# schematic.net
KiCad netlist of a schematic drawn in EAGLE
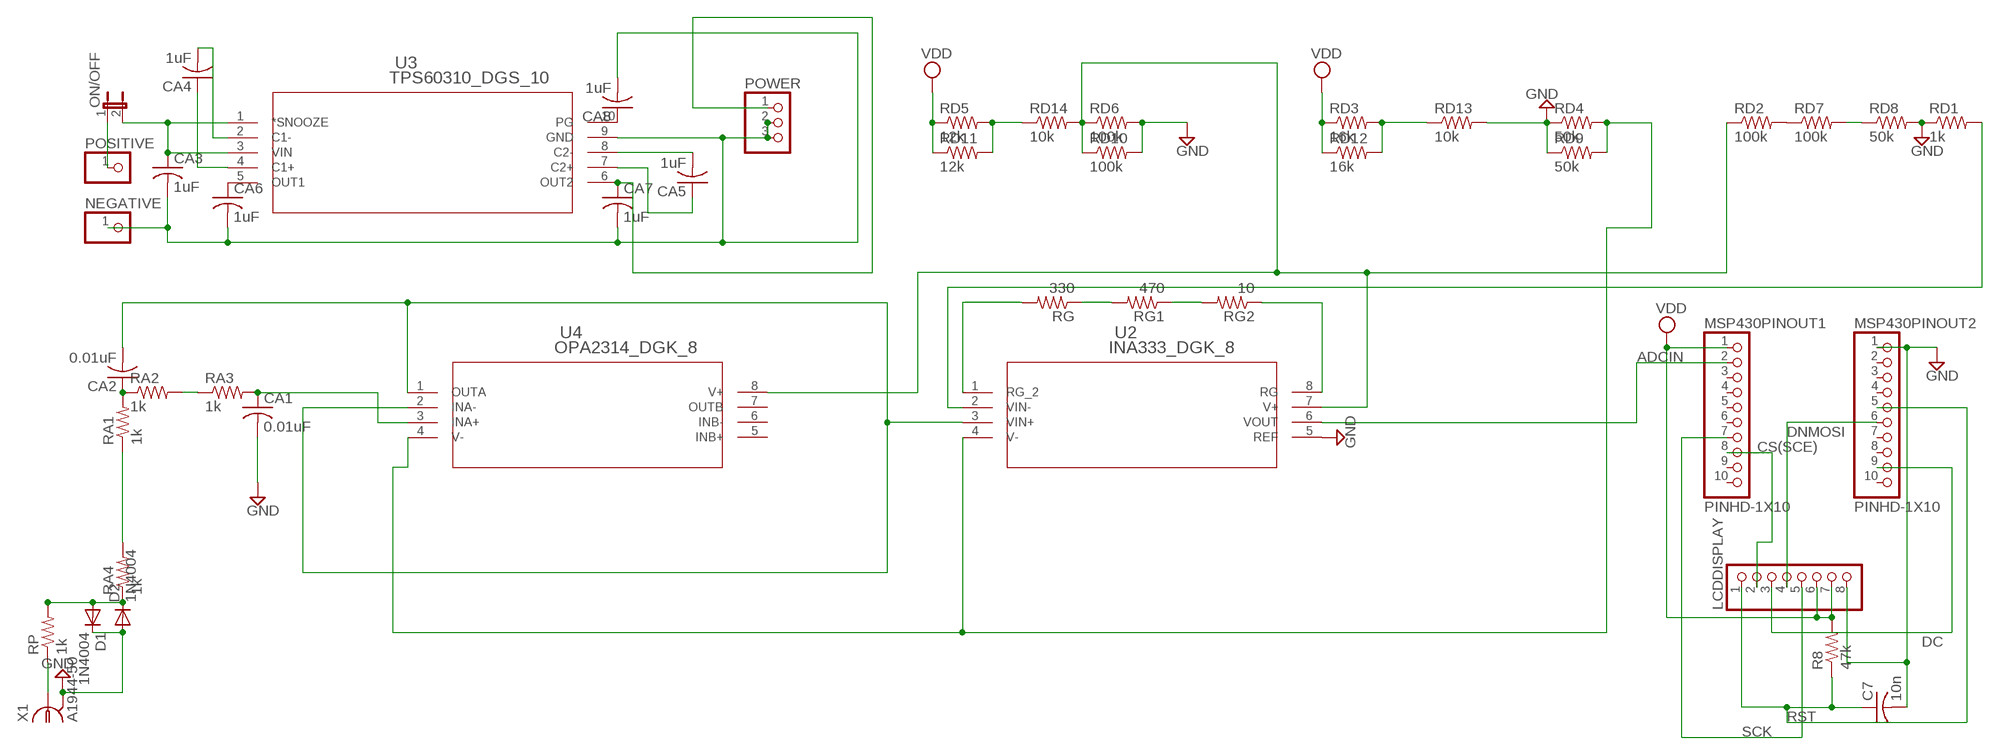
[diagram p0: schematic, sheet 1]

(export (version "E")
  (design (tool "Eeschema 10.0.6"))
  (components
    (comp (ref "C7")
      (value "10n")
      (footprint "eagle-import:C025-024X044")
      (libsource (lib "eagle-import") (part "C-US025-024X044"))
    )
    (comp (ref "CA1")
      (value "0.01uF")
      (footprint "eagle-import:C025-024X044")
      (libsource (lib "eagle-import") (part "C-US025-024X044"))
    )
    (comp (ref "CA2")
      (value "0.01uF")
      (footprint "eagle-import:C025-024X044")
      (libsource (lib "eagle-import") (part "C-US025-024X044"))
    )
    (comp (ref "CA3")
      (value "1uF")
      (footprint "eagle-import:C025-024X044")
      (libsource (lib "eagle-import") (part "C-US025-024X044"))
    )
    (comp (ref "CA4")
      (value "1uF")
      (footprint "eagle-import:C025-024X044")
      (libsource (lib "eagle-import") (part "C-US025-024X044"))
    )
    (comp (ref "CA5")
      (value "1uF")
      (footprint "eagle-import:C025-024X044")
      (libsource (lib "eagle-import") (part "C-US025-024X044"))
    )
    (comp (ref "CA6")
      (value "1uF")
      (footprint "eagle-import:C025-024X044")
      (libsource (lib "eagle-import") (part "C-US025-024X044"))
    )
    (comp (ref "CA7")
      (value "1uF")
      (footprint "eagle-import:C025-024X044")
      (libsource (lib "eagle-import") (part "C-US025-024X044"))
    )
    (comp (ref "CA8")
      (value "1uF")
      (footprint "eagle-import:C025-024X044")
      (libsource (lib "eagle-import") (part "C-US025-024X044"))
    )
    (comp (ref "D1")
      (value "1N4004")
      (footprint "eagle-import:DO41-10")
      (libsource (lib "eagle-import") (part "1N4004"))
    )
    (comp (ref "D2")
      (value "1N4004")
      (footprint "eagle-import:DO41-10")
      (libsource (lib "eagle-import") (part "1N4004"))
    )
    (comp (ref "LCDDISPLAY")
      (value "PINHD-1X8BIG")
      (footprint "eagle-import:1X08-BIG")
      (libsource (lib "eagle-import") (part "PINHD-1X8BIG"))
    )
    (comp (ref "MSP430PINOUT1")
      (value "PINHD-1X10")
      (footprint "eagle-import:1X10-BIG")
      (libsource (lib "eagle-import") (part "PINHD-1X10"))
    )
    (comp (ref "MSP430PINOUT2")
      (value "PINHD-1X10")
      (footprint "eagle-import:1X10-BIG")
      (libsource (lib "eagle-import") (part "PINHD-1X10"))
    )
    (comp (ref "NEGATIVE")
      (value "PINHD-1X1")
      (footprint "eagle-import:1X01")
      (libsource (lib "eagle-import") (part "PINHD-1X1"))
    )
    (comp (ref "ON/OFF")
      (value "JP1E")
      (footprint "eagle-import:JP1")
      (libsource (lib "eagle-import") (part "JP1E"))
    )
    (comp (ref "POSITIVE")
      (value "PINHD-1X1")
      (footprint "eagle-import:1X01")
      (libsource (lib "eagle-import") (part "PINHD-1X1"))
    )
    (comp (ref "POWER")
      (value "PINHD-1X3")
      (footprint "eagle-import:1X03")
      (libsource (lib "eagle-import") (part "PINHD-1X3"))
    )
    (comp (ref "R8")
      (value "47k")
      (footprint "eagle-import:0204_7")
      (libsource (lib "eagle-import") (part "R-US_0204/7"))
    )
    (comp (ref "RA1")
      (value "1k")
      (footprint "eagle-import:0204_7")
      (libsource (lib "eagle-import") (part "R-US_0204/7"))
    )
    (comp (ref "RA2")
      (value "1k")
      (footprint "eagle-import:0204_7")
      (libsource (lib "eagle-import") (part "R-US_0204/7"))
    )
    (comp (ref "RA3")
      (value "1k")
      (footprint "eagle-import:0204_7")
      (libsource (lib "eagle-import") (part "R-US_0204/7"))
    )
    (comp (ref "RA4")
      (value "1k")
      (footprint "eagle-import:0204_7")
      (libsource (lib "eagle-import") (part "R-US_0204/7"))
    )
    (comp (ref "RD1")
      (value "1k")
      (footprint "eagle-import:0204_7")
      (libsource (lib "eagle-import") (part "R-US_0204/7"))
    )
    (comp (ref "RD2")
      (value "100k")
      (footprint "eagle-import:0204_7")
      (libsource (lib "eagle-import") (part "R-US_0204/7"))
    )
    (comp (ref "RD3")
      (value "16k")
      (footprint "eagle-import:0204_7")
      (libsource (lib "eagle-import") (part "R-US_0204/7"))
    )
    (comp (ref "RD4")
      (value "50k")
      (footprint "eagle-import:0204_7")
      (libsource (lib "eagle-import") (part "R-US_0204/7"))
    )
    (comp (ref "RD5")
      (value "12k")
      (footprint "eagle-import:0204_7")
      (libsource (lib "eagle-import") (part "R-US_0204/7"))
    )
    (comp (ref "RD6")
      (value "100k")
      (footprint "eagle-import:0204_7")
      (libsource (lib "eagle-import") (part "R-US_0204/7"))
    )
    (comp (ref "RD7")
      (value "100k")
      (footprint "eagle-import:0204_7")
      (libsource (lib "eagle-import") (part "R-US_0204/7"))
    )
    (comp (ref "RD8")
      (value "50k")
      (footprint "eagle-import:0204_7")
      (libsource (lib "eagle-import") (part "R-US_0204/7"))
    )
    (comp (ref "RD9")
      (value "50k")
      (footprint "eagle-import:0204_7")
      (libsource (lib "eagle-import") (part "R-US_0204/7"))
    )
    (comp (ref "RD10")
      (value "100k")
      (footprint "eagle-import:0204_7")
      (libsource (lib "eagle-import") (part "R-US_0204/7"))
    )
    (comp (ref "RD11")
      (value "12k")
      (footprint "eagle-import:0204_7")
      (libsource (lib "eagle-import") (part "R-US_0204/7"))
    )
    (comp (ref "RD12")
      (value "16k")
      (footprint "eagle-import:0204_7")
      (libsource (lib "eagle-import") (part "R-US_0204/7"))
    )
    (comp (ref "RD13")
      (value "10k")
      (footprint "eagle-import:0204_7")
      (libsource (lib "eagle-import") (part "R-US_0204/7"))
    )
    (comp (ref "RD14")
      (value "10k")
      (footprint "eagle-import:0204_7")
      (libsource (lib "eagle-import") (part "R-US_0204/7"))
    )
    (comp (ref "RG")
      (value "330")
      (footprint "eagle-import:0204_7")
      (libsource (lib "eagle-import") (part "R-US_0204/7"))
    )
    (comp (ref "RG1")
      (value "470")
      (footprint "eagle-import:0204_7")
      (libsource (lib "eagle-import") (part "R-US_0204/7"))
    )
    (comp (ref "RG2")
      (value "10")
      (footprint "eagle-import:0204_7")
      (libsource (lib "eagle-import") (part "R-US_0204/7"))
    )
    (comp (ref "RP")
      (value "1k")
      (footprint "eagle-import:0204_7")
      (libsource (lib "eagle-import") (part "R-US_0204/7"))
    )
    (comp (ref "U2")
      (value "INA333_DGK_8")
      (footprint "eagle-import:DGK8")
      (fields
        (field (name "GENERIC_PART_NUMBER") "INA333")
        (field (name "MANUFACTURER") "Texas Instruments")
        (field (name "MANUFACTURER_PART_NUMBER") "ina333_dgk_8")
      )
      (libsource (lib "eagle-import") (part "INA333_DGK_8"))
    )
    (comp (ref "U3")
      (value "TPS60310_DGS_10")
      (footprint "eagle-import:DGS10")
      (fields
        (field (name "GENERIC_PART_NUMBER") "TPS60310")
        (field (name "MANUFACTURER") "Texas Instruments")
        (field (name "MANUFACTURER_PART_NUMBER") "tps60310_dgs_10")
      )
      (libsource (lib "eagle-import") (part "TPS60310_DGS_10"))
    )
    (comp (ref "U4")
      (value "OPA2314_DGK_8")
      (footprint "eagle-import:DGK8")
      (fields
        (field (name "GENERIC_PART_NUMBER") "OPA2314")
        (field (name "MANUFACTURER") "Texas Instruments")
        (field (name "MANUFACTURER_PART_NUMBER") "opa2314_dgk_8")
      )
      (libsource (lib "eagle-import") (part "OPA2314_DGK_8"))
    )
    (comp (ref "X1")
      (value "A1944-50")
      (footprint "eagle-import:A1944")
      (libsource (lib "eagle-import") (part "A1944-50"))
    )
  )
  (nets
    (net (code "1") (name "/ADCIN") (class "Default")
      (node (ref "MSP430PINOUT1") (pin "2") (pinfunction "2_2") (pintype "passive"))
      (node (ref "U2") (pin "6") (pinfunction "VOUT_6") (pintype "output"))
    )
    (net (code "2") (name "/CS(SCE)") (class "Default")
      (node (ref "LCDDISPLAY") (pin "2") (pinfunction "2_2") (pintype "passive"))
      (node (ref "MSP430PINOUT1") (pin "8") (pinfunction "8_8") (pintype "passive"))
    )
    (net (code "3") (name "/DC") (class "Default")
      (node (ref "LCDDISPLAY") (pin "3") (pinfunction "3_3") (pintype "passive"))
      (node (ref "MSP430PINOUT2") (pin "9") (pinfunction "9_9") (pintype "passive"))
    )
    (net (code "4") (name "/DNMOSI") (class "Default")
      (node (ref "LCDDISPLAY") (pin "4") (pinfunction "4_4") (pintype "passive"))
      (node (ref "MSP430PINOUT2") (pin "6") (pinfunction "6_6") (pintype "passive"))
    )
    (net (code "5") (name "/RST") (class "Default")
      (node (ref "C7") (pin "1") (pinfunction "1_1") (pintype "passive"))
      (node (ref "LCDDISPLAY") (pin "1") (pinfunction "1_1") (pintype "passive"))
      (node (ref "MSP430PINOUT2") (pin "5") (pinfunction "5_5") (pintype "passive"))
      (node (ref "R8") (pin "1") (pinfunction "1_1") (pintype "passive"))
    )
    (net (code "6") (name "/SCK") (class "Default")
      (node (ref "LCDDISPLAY") (pin "5") (pinfunction "5_5") (pintype "passive"))
      (node (ref "MSP430PINOUT1") (pin "7") (pinfunction "7_7") (pintype "passive"))
    )
    (net (code "7") (name "GND") (class "Default")
      (node (ref "C7") (pin "2") (pinfunction "2_2") (pintype "passive"))
      (node (ref "CA1") (pin "2") (pinfunction "2_2") (pintype "passive"))
      (node (ref "D1") (pin "C") (pinfunction "C_C") (pintype "passive"))
      (node (ref "D2") (pin "A") (pinfunction "A_A") (pintype "passive"))
      (node (ref "LCDDISPLAY") (pin "8") (pinfunction "8_8") (pintype "passive"))
      (node (ref "MSP430PINOUT2") (pin "1") (pinfunction "1_1") (pintype "passive"))
      (node (ref "RD1") (pin "1") (pinfunction "1_1") (pintype "passive"))
      (node (ref "RD10") (pin "2") (pinfunction "2_2") (pintype "passive"))
      (node (ref "RD13") (pin "2") (pinfunction "2_2") (pintype "passive"))
      (node (ref "RD4") (pin "1") (pinfunction "1_1") (pintype "passive"))
      (node (ref "RD6") (pin "2") (pinfunction "2_2") (pintype "passive"))
      (node (ref "RD8") (pin "2") (pinfunction "2_2") (pintype "passive"))
      (node (ref "RD9") (pin "1") (pinfunction "1_1") (pintype "passive"))
      (node (ref "U2") (pin "5") (pinfunction "REF_5") (pintype "passive"))
      (node (ref "X1") (pin "2") (pinfunction "GND_2") (pintype "power_in"))
    )
    (net (code "8") (name "Net-(CA2-Pad1)") (class "Default")
      (node (ref "CA2") (pin "1") (pinfunction "1_1") (pintype "passive"))
      (node (ref "RA1") (pin "2") (pinfunction "2_2") (pintype "passive"))
      (node (ref "RA2") (pin "1") (pinfunction "1_1") (pintype "passive"))
    )
    (net (code "9") (name "Net-(D1-PadA)") (class "Default")
      (node (ref "D1") (pin "A") (pinfunction "A_A") (pintype "passive"))
      (node (ref "D2") (pin "C") (pinfunction "C_C") (pintype "passive"))
      (node (ref "RA4") (pin "1") (pinfunction "1_1") (pintype "passive"))
      (node (ref "RP") (pin "2") (pinfunction "2_2") (pintype "passive"))
    )
    (net (code "10") (name "Net-(ON/OFF-Pad1)") (class "Default")
      (node (ref "ON/OFF") (pin "1") (pinfunction "1_1") (pintype "passive"))
      (node (ref "POSITIVE") (pin "1") (pinfunction "1_1") (pintype "passive"))
    )
    (net (code "11") (name "Net-(RA1-Pad1)") (class "Default")
      (node (ref "RA1") (pin "1") (pinfunction "1_1") (pintype "passive"))
      (node (ref "RA4") (pin "2") (pinfunction "2_2") (pintype "passive"))
    )
    (net (code "12") (name "Net-(RA2-Pad2)") (class "Default")
      (node (ref "RA2") (pin "2") (pinfunction "2_2") (pintype "passive"))
      (node (ref "RA3") (pin "1") (pinfunction "1_1") (pintype "passive"))
    )
    (net (code "13") (name "Net-(RD2-Pad2)") (class "Default")
      (node (ref "RD2") (pin "2") (pinfunction "2_2") (pintype "passive"))
      (node (ref "RD7") (pin "1") (pinfunction "1_1") (pintype "passive"))
    )
    (net (code "14") (name "Net-(RD7-Pad2)") (class "Default")
      (node (ref "RD7") (pin "2") (pinfunction "2_2") (pintype "passive"))
      (node (ref "RD8") (pin "1") (pinfunction "1_1") (pintype "passive"))
    )
    (net (code "15") (name "Net-(RD11-Pad2)") (class "Default")
      (node (ref "RD11") (pin "2") (pinfunction "2_2") (pintype "passive"))
      (node (ref "RD14") (pin "1") (pinfunction "1_1") (pintype "passive"))
      (node (ref "RD5") (pin "2") (pinfunction "2_2") (pintype "passive"))
    )
    (net (code "16") (name "Net-(RD12-Pad2)") (class "Default")
      (node (ref "RD12") (pin "2") (pinfunction "2_2") (pintype "passive"))
      (node (ref "RD13") (pin "1") (pinfunction "1_1") (pintype "passive"))
      (node (ref "RD3") (pin "2") (pinfunction "2_2") (pintype "passive"))
    )
    (net (code "17") (name "Net-(RG-Pad1)") (class "Default")
      (node (ref "RG") (pin "1") (pinfunction "1_1") (pintype "passive"))
      (node (ref "RG1") (pin "2") (pinfunction "2_2") (pintype "passive"))
    )
    (net (code "18") (name "Net-(RG1-Pad1)") (class "Default")
      (node (ref "RG1") (pin "1") (pinfunction "1_1") (pintype "passive"))
      (node (ref "RG2") (pin "2") (pinfunction "2_2") (pintype "passive"))
    )
    (net (code "19") (name "Net-(RP-Pad1)") (class "Default")
      (node (ref "RP") (pin "1") (pinfunction "1_1") (pintype "passive"))
      (node (ref "X1") (pin "1") (pinfunction "1_1") (pintype "passive"))
    )
    (net (code "20") (name "Net-(U2-RG)") (class "Default")
      (node (ref "RG2") (pin "1") (pinfunction "1_1") (pintype "passive"))
      (node (ref "U2") (pin "8") (pinfunction "RG_8") (pintype "passive"))
    )
    (net (code "21") (name "Net-(U2-RG_2)") (class "Default")
      (node (ref "RG") (pin "2") (pinfunction "2_2") (pintype "passive"))
      (node (ref "U2") (pin "1") (pinfunction "RG_2_1") (pintype "passive"))
    )
    (net (code "22") (name "Net-(U2-V+)") (class "Default")
      (node (ref "RD10") (pin "1") (pinfunction "1_1") (pintype "passive"))
      (node (ref "RD14") (pin "2") (pinfunction "2_2") (pintype "passive"))
      (node (ref "RD2") (pin "1") (pinfunction "1_1") (pintype "passive"))
      (node (ref "RD6") (pin "1") (pinfunction "1_1") (pintype "passive"))
      (node (ref "U2") (pin "7") (pinfunction "V+_7") (pintype "power_in"))
      (node (ref "U4") (pin "8") (pinfunction "V+_8") (pintype "power_in"))
    )
    (net (code "23") (name "Net-(U2-V-)") (class "Default")
      (node (ref "RD4") (pin "2") (pinfunction "2_2") (pintype "passive"))
      (node (ref "RD9") (pin "2") (pinfunction "2_2") (pintype "passive"))
      (node (ref "U2") (pin "4") (pinfunction "V-_4") (pintype "power_in"))
      (node (ref "U4") (pin "4") (pinfunction "V-_4") (pintype "power_in"))
    )
    (net (code "24") (name "Net-(U2-VIN+)") (class "Default")
      (node (ref "CA2") (pin "2") (pinfunction "2_2") (pintype "passive"))
      (node (ref "U2") (pin "3") (pinfunction "VIN+_3") (pintype "input"))
      (node (ref "U4") (pin "1") (pinfunction "OUTA_1") (pintype "output"))
      (node (ref "U4") (pin "2") (pinfunction "INA-_2") (pintype "input"))
    )
    (net (code "25") (name "Net-(U2-VIN-)") (class "Default")
      (node (ref "RD1") (pin "2") (pinfunction "2_2") (pintype "passive"))
      (node (ref "U2") (pin "2") (pinfunction "VIN-_2") (pintype "input"))
    )
    (net (code "26") (name "Net-(U3-*SNOOZE)") (class "Default")
      (node (ref "CA3") (pin "1") (pinfunction "1_1") (pintype "passive"))
      (node (ref "ON/OFF") (pin "2") (pinfunction "2_2") (pintype "passive"))
      (node (ref "U3") (pin "1") (pinfunction "*SNOOZE_1") (pintype "input"))
      (node (ref "U3") (pin "3") (pinfunction "VIN_3") (pintype "input"))
    )
    (net (code "27") (name "Net-(U3-C1+)") (class "Default")
      (node (ref "CA4") (pin "1") (pinfunction "1_1") (pintype "passive"))
      (node (ref "U3") (pin "4") (pinfunction "C1+_4") (pintype "passive"))
    )
    (net (code "28") (name "Net-(U3-C1-)") (class "Default")
      (node (ref "CA4") (pin "2") (pinfunction "2_2") (pintype "passive"))
      (node (ref "U3") (pin "2") (pinfunction "C1-_2") (pintype "passive"))
    )
    (net (code "29") (name "Net-(U3-C2+)") (class "Default")
      (node (ref "CA5") (pin "1") (pinfunction "1_1") (pintype "passive"))
      (node (ref "U3") (pin "7") (pinfunction "C2+_7") (pintype "passive"))
    )
    (net (code "30") (name "Net-(U3-C2-)") (class "Default")
      (node (ref "CA5") (pin "2") (pinfunction "2_2") (pintype "passive"))
      (node (ref "U3") (pin "8") (pinfunction "C2-_8") (pintype "passive"))
    )
    (net (code "31") (name "Net-(U3-GND)") (class "Default")
      (node (ref "CA3") (pin "2") (pinfunction "2_2") (pintype "passive"))
      (node (ref "CA6") (pin "2") (pinfunction "2_2") (pintype "passive"))
      (node (ref "CA7") (pin "2") (pinfunction "2_2") (pintype "passive"))
      (node (ref "CA8") (pin "2") (pinfunction "2_2") (pintype "passive"))
      (node (ref "NEGATIVE") (pin "1") (pinfunction "1_1") (pintype "passive"))
      (node (ref "POWER") (pin "2") (pinfunction "2_2") (pintype "passive"))
      (node (ref "POWER") (pin "3") (pinfunction "3_3") (pintype "passive"))
      (node (ref "U3") (pin "9") (pinfunction "GND_9") (pintype "power_in"))
    )
    (net (code "32") (name "Net-(U3-OUT1)") (class "Default")
      (node (ref "CA6") (pin "1") (pinfunction "1_1") (pintype "passive"))
      (node (ref "U3") (pin "5") (pinfunction "OUT1_5") (pintype "output"))
    )
    (net (code "33") (name "Net-(U3-OUT2)") (class "Default")
      (node (ref "CA7") (pin "1") (pinfunction "1_1") (pintype "passive"))
      (node (ref "POWER") (pin "1") (pinfunction "1_1") (pintype "passive"))
      (node (ref "U3") (pin "6") (pinfunction "OUT2_6") (pintype "output"))
    )
    (net (code "34") (name "Net-(U3-PG)") (class "Default")
      (node (ref "CA8") (pin "1") (pinfunction "1_1") (pintype "passive"))
      (node (ref "U3") (pin "10") (pinfunction "PG_10") (pintype "output"))
    )
    (net (code "35") (name "Net-(U4-INA+)") (class "Default")
      (node (ref "CA1") (pin "1") (pinfunction "1_1") (pintype "passive"))
      (node (ref "RA3") (pin "2") (pinfunction "2_2") (pintype "passive"))
      (node (ref "U4") (pin "3") (pinfunction "INA+_3") (pintype "input"))
    )
    (net (code "36") (name "VDD") (class "Default")
      (node (ref "LCDDISPLAY") (pin "6") (pinfunction "6_6") (pintype "passive"))
      (node (ref "LCDDISPLAY") (pin "7") (pinfunction "7_7") (pintype "passive"))
      (node (ref "MSP430PINOUT1") (pin "1") (pinfunction "1_1") (pintype "passive"))
      (node (ref "R8") (pin "2") (pinfunction "2_2") (pintype "passive"))
      (node (ref "RD11") (pin "1") (pinfunction "1_1") (pintype "passive"))
      (node (ref "RD12") (pin "1") (pinfunction "1_1") (pintype "passive"))
      (node (ref "RD3") (pin "1") (pinfunction "1_1") (pintype "passive"))
      (node (ref "RD5") (pin "1") (pinfunction "1_1") (pintype "passive"))
    )
    (net (code "37") (name "unconnected-(MSP430PINOUT1-Pad3)") (class "Default")
      (node (ref "MSP430PINOUT1") (pin "3") (pinfunction "3_3") (pintype "passive"))
    )
    (net (code "38") (name "unconnected-(MSP430PINOUT1-Pad4)") (class "Default")
      (node (ref "MSP430PINOUT1") (pin "4") (pinfunction "4_4") (pintype "passive"))
    )
    (net (code "39") (name "unconnected-(MSP430PINOUT1-Pad5)") (class "Default")
      (node (ref "MSP430PINOUT1") (pin "5") (pinfunction "5_5") (pintype "passive"))
    )
    (net (code "40") (name "unconnected-(MSP430PINOUT1-Pad6)") (class "Default")
      (node (ref "MSP430PINOUT1") (pin "6") (pinfunction "6_6") (pintype "passive"))
    )
    (net (code "41") (name "unconnected-(MSP430PINOUT1-Pad9)") (class "Default")
      (node (ref "MSP430PINOUT1") (pin "9") (pinfunction "9_9") (pintype "passive"))
    )
    (net (code "42") (name "unconnected-(MSP430PINOUT1-Pad10)") (class "Default")
      (node (ref "MSP430PINOUT1") (pin "10") (pinfunction "10_10") (pintype "passive"))
    )
    (net (code "43") (name "unconnected-(MSP430PINOUT2-Pad2)") (class "Default")
      (node (ref "MSP430PINOUT2") (pin "2") (pinfunction "2_2") (pintype "passive"))
    )
    (net (code "44") (name "unconnected-(MSP430PINOUT2-Pad3)") (class "Default")
      (node (ref "MSP430PINOUT2") (pin "3") (pinfunction "3_3") (pintype "passive"))
    )
    (net (code "45") (name "unconnected-(MSP430PINOUT2-Pad4)") (class "Default")
      (node (ref "MSP430PINOUT2") (pin "4") (pinfunction "4_4") (pintype "passive"))
    )
    (net (code "46") (name "unconnected-(MSP430PINOUT2-Pad7)") (class "Default")
      (node (ref "MSP430PINOUT2") (pin "7") (pinfunction "7_7") (pintype "passive"))
    )
    (net (code "47") (name "unconnected-(MSP430PINOUT2-Pad8)") (class "Default")
      (node (ref "MSP430PINOUT2") (pin "8") (pinfunction "8_8") (pintype "passive"))
    )
    (net (code "48") (name "unconnected-(MSP430PINOUT2-Pad10)") (class "Default")
      (node (ref "MSP430PINOUT2") (pin "10") (pinfunction "10_10") (pintype "passive"))
    )
    (net (code "49") (name "unconnected-(U4-INB+-Pad5)") (class "Default")
      (node (ref "U4") (pin "5") (pinfunction "INB+_5") (pintype "input"))
    )
    (net (code "50") (name "unconnected-(U4-INB--Pad6)") (class "Default")
      (node (ref "U4") (pin "6") (pinfunction "INB-_6") (pintype "input"))
    )
    (net (code "51") (name "unconnected-(U4-OUTB-Pad7)") (class "Default")
      (node (ref "U4") (pin "7") (pinfunction "OUTB_7") (pintype "output"))
    )
  )
)
